# USBserial.net
KiCad netlist of a schematic drawn in Altium Designer
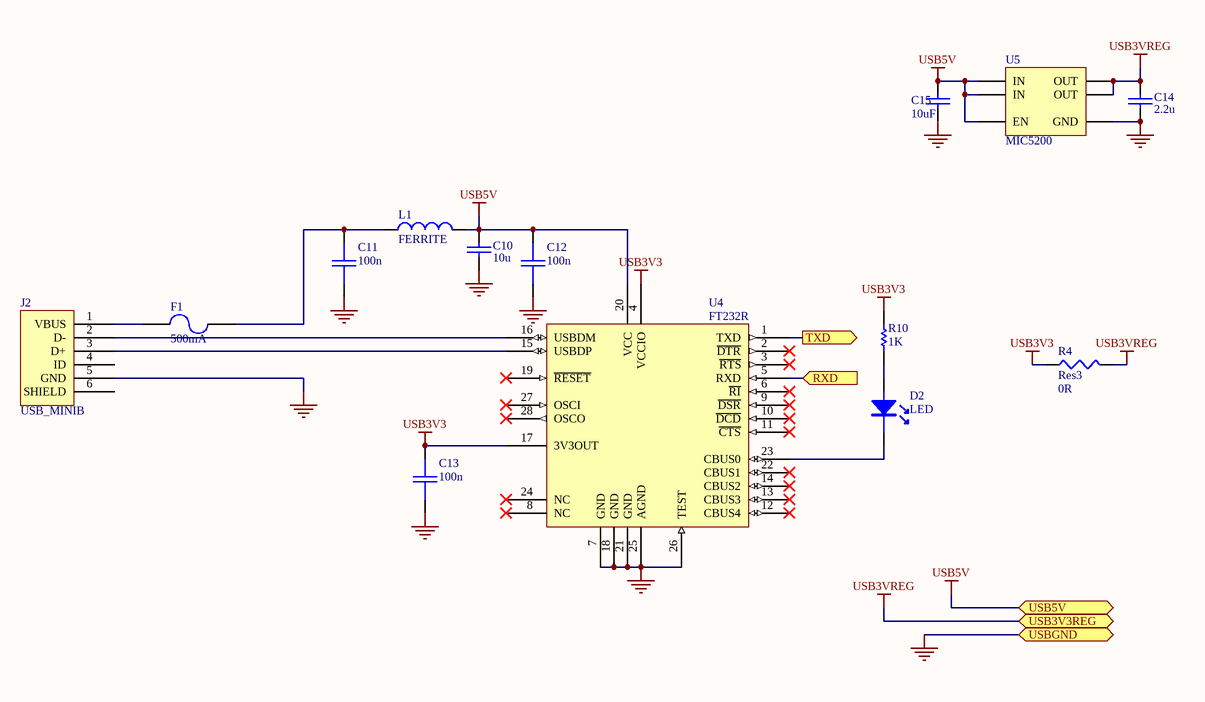
[diagram p0: USBserial.SchDoc]

(export (version "E")
  (design (tool "Eeschema 10.0.6"))
  (components
    (comp (ref "C10")
      (value "10u")
      (footprint "0805")
      (description "Capacitor")
      (libsource (lib "*") (part "CAP"))
    )
    (comp (ref "C11")
      (value "100n")
      (footprint "0603")
      (description "Capacitor")
      (libsource (lib "RCLDQ") (part "CAP"))
    )
    (comp (ref "C12")
      (value "100n")
      (footprint "0603")
      (description "Capacitor")
      (libsource (lib "RCLDQ") (part "CAP"))
    )
    (comp (ref "C13")
      (value "100n")
      (footprint "0603")
      (description "Capacitor")
      (libsource (lib "RCLDQ") (part "CAP"))
    )
    (comp (ref "C14")
      (value "2.2u")
      (footprint "0603")
      (description "Capacitor")
      (libsource (lib "*") (part "CAP"))
    )
    (comp (ref "C15")
      (value "10uF")
      (footprint "0805")
      (description "Capacitor")
      (fields (field (name "Comment") "10u"))
      (libsource (lib "*") (part "CAP"))
    )
    (comp (ref "D2") (value "LED") (footprint "3mmLED") (libsource (lib "RCLDQ") (part "LED")))
    (comp (ref "F1")
      (value "500mA")
      (footprint "LITTELFUSE-154")
      (description "Fuse")
      (libsource (lib "*") (part "FUSE2"))
    )
    (comp (ref "J2")
      (value "USB_MINIB")
      (footprint "Con USB:USB/SM0.8-6H5")
      (description "USB Mini B Connector")
      (libsource (lib "sion") (part "USB_miniB_SMT"))
    )
    (comp (ref "L1")
      (value "FERRITE")
      (footprint "0603")
      (description "Inductor")
      (fields (field (name "MANUFACTURER") "Generic Components"))
      (libsource (lib "RCLDQ") (part "INDUCTOR"))
    )
    (comp (ref "R4")
      (value "Res3")
      (footprint "0603")
      (description "Resistor")
      (fields (field (name "ALTIUM_VALUE") "0R") (field (name "PUBLISHER") "Altium Limited"))
      (libsource (lib "Miscellaneous Devices") (part "Res3"))
    )
    (comp (ref "R10")
      (value "1K")
      (footprint "0603")
      (description "Semiconductor Resistor")
      (libsource (lib "Miscellaneous Devices") (part "Res Semi"))
    )
    (comp (ref "U4")
      (value "FT232R")
      (footprint "SSOP28w")
      (description "USB UART IC")
      (libsource (lib "MiscellaneousIC") (part "FT232R"))
    )
    (comp (ref "U5")
      (value "MIC5200")
      (footprint "SO8")
      (description "MIC5200 - SO8")
      (libsource (lib "*") (part "MIC5200"))
    )
  )
  (nets
    (net (code "1") (name "/RXD") (class "Default")
      (node (ref "U4") (pin "5") (pinfunction "RXD_5") (pintype "input"))
    )
    (net (code "2") (name "/TXD") (class "Default")
      (node (ref "U4") (pin "1") (pinfunction "TXD_1") (pintype "output"))
    )
    (net (code "3") (name "Net-(C11-Pad1)") (class "Default")
      (node (ref "C11") (pin "1") (pinfunction "1_1") (pintype "passive"))
      (node (ref "F1") (pin "2") (pinfunction "2_2") (pintype "passive"))
      (node (ref "L1") (pin "1") (pinfunction "1_1") (pintype "passive"))
    )
    (net (code "4") (name "Net-(D2-PadA)") (class "Default")
      (node (ref "D2") (pin "A") (pinfunction "A_A") (pintype "passive"))
      (node (ref "R10") (pin "1") (pinfunction "1_1") (pintype "passive"))
    )
    (net (code "5") (name "Net-(J2-D+)") (class "Default")
      (node (ref "J2") (pin "3") (pinfunction "D+_3") (pintype "passive"))
      (node (ref "U4") (pin "15") (pinfunction "USBDP_15") (pintype "bidirectional"))
    )
    (net (code "6") (name "Net-(J2-D-)") (class "Default")
      (node (ref "J2") (pin "2") (pinfunction "D-_2") (pintype "passive"))
      (node (ref "U4") (pin "16") (pinfunction "USBDM_16") (pintype "bidirectional"))
    )
    (net (code "7") (name "Net-(J2-VBUS)") (class "Default")
      (node (ref "F1") (pin "1") (pinfunction "1_1") (pintype "passive"))
      (node (ref "J2") (pin "1") (pinfunction "VBUS_1") (pintype "passive"))
    )
    (net (code "8") (name "Net-(U4-CBUS0)") (class "Default")
      (node (ref "D2") (pin "K") (pinfunction "K_K") (pintype "passive"))
      (node (ref "U4") (pin "23") (pinfunction "CBUS0_23") (pintype "bidirectional"))
    )
    (net (code "9") (name "USB3V3") (class "Default")
      (node (ref "C13") (pin "1") (pinfunction "1_1") (pintype "passive"))
      (node (ref "R10") (pin "2") (pinfunction "2_2") (pintype "passive"))
      (node (ref "R4") (pin "1") (pinfunction "1_1") (pintype "passive"))
      (node (ref "U4") (pin "17") (pinfunction "3V3OUT_17") (pintype "power_in"))
      (node (ref "U4") (pin "4") (pinfunction "VCCIO_4") (pintype "power_in"))
    )
    (net (code "10") (name "USB3VREG") (class "Default")
      (node (ref "C14") (pin "2") (pinfunction "2_2") (pintype "passive"))
      (node (ref "R4") (pin "2") (pinfunction "2_2") (pintype "passive"))
      (node (ref "U5") (pin "1") (pinfunction "OUT_1") (pintype "passive"))
      (node (ref "U5") (pin "2") (pinfunction "OUT_2") (pintype "passive"))
    )
    (net (code "11") (name "USB5V") (class "Default")
      (node (ref "C10") (pin "2") (pinfunction "2_2") (pintype "passive"))
      (node (ref "C12") (pin "1") (pinfunction "1_1") (pintype "passive"))
      (node (ref "C15") (pin "1") (pinfunction "1_1") (pintype "passive"))
      (node (ref "L1") (pin "2") (pinfunction "2_2") (pintype "passive"))
      (node (ref "U4") (pin "20") (pinfunction "VCC_20") (pintype "power_in"))
      (node (ref "U5") (pin "5") (pinfunction "EN_5") (pintype "passive"))
      (node (ref "U5") (pin "7") (pinfunction "IN_7") (pintype "passive"))
      (node (ref "U5") (pin "8") (pinfunction "IN_8") (pintype "passive"))
    )
    (net (code "12") (name "USBGND") (class "Default")
      (node (ref "C10") (pin "1") (pinfunction "1_1") (pintype "passive"))
      (node (ref "C11") (pin "2") (pinfunction "2_2") (pintype "passive"))
      (node (ref "C12") (pin "2") (pinfunction "2_2") (pintype "passive"))
      (node (ref "C13") (pin "2") (pinfunction "2_2") (pintype "passive"))
      (node (ref "C14") (pin "1") (pinfunction "1_1") (pintype "passive"))
      (node (ref "C15") (pin "2") (pinfunction "2_2") (pintype "passive"))
      (node (ref "J2") (pin "5") (pinfunction "GND_5") (pintype "passive"))
      (node (ref "U4") (pin "18") (pinfunction "GND_18") (pintype "power_in"))
      (node (ref "U4") (pin "21") (pinfunction "GND_21") (pintype "power_in"))
      (node (ref "U4") (pin "25") (pinfunction "AGND_25") (pintype "power_in"))
      (node (ref "U4") (pin "26") (pinfunction "TEST_26") (pintype "input"))
      (node (ref "U4") (pin "7") (pinfunction "GND_7") (pintype "power_in"))
      (node (ref "U5") (pin "4") (pinfunction "GND_4") (pintype "passive"))
    )
    (net (code "13") (name "unconnected-(J2-ID-Pad4)") (class "Default")
      (node (ref "J2") (pin "4") (pinfunction "ID_4") (pintype "passive"))
    )
    (net (code "14") (name "unconnected-(J2-SHIELD-Pad6)") (class "Default")
      (node (ref "J2") (pin "6") (pinfunction "SHIELD_6") (pintype "passive"))
    )
    (net (code "15") (name "unconnected-(U4-CBUS1-Pad22)") (class "Default")
      (node (ref "U4") (pin "22") (pinfunction "CBUS1_22") (pintype "bidirectional+no_connect"))
    )
    (net (code "16") (name "unconnected-(U4-CBUS2-Pad14)") (class "Default")
      (node (ref "U4") (pin "14") (pinfunction "CBUS2_14") (pintype "bidirectional+no_connect"))
    )
    (net (code "17") (name "unconnected-(U4-CBUS3-Pad13)") (class "Default")
      (node (ref "U4") (pin "13") (pinfunction "CBUS3_13") (pintype "bidirectional+no_connect"))
    )
    (net (code "18") (name "unconnected-(U4-CBUS4-Pad12)") (class "Default")
      (node (ref "U4") (pin "12") (pinfunction "CBUS4_12") (pintype "bidirectional+no_connect"))
    )
    (net (code "19") (name "unconnected-(U4-NC-Pad8)") (class "Default")
      (node (ref "U4") (pin "8") (pinfunction "NC_8") (pintype "passive+no_connect"))
    )
    (net (code "20") (name "unconnected-(U4-NC-Pad24)") (class "Default")
      (node (ref "U4") (pin "24") (pinfunction "NC_24") (pintype "passive+no_connect"))
    )
    (net (code "21") (name "unconnected-(U4-OSCI-Pad27)") (class "Default")
      (node (ref "U4") (pin "27") (pinfunction "OSCI_27") (pintype "input+no_connect"))
    )
    (net (code "22") (name "unconnected-(U4-OSCO-Pad28)") (class "Default")
      (node (ref "U4") (pin "28") (pinfunction "OSCO_28") (pintype "output+no_connect"))
    )
    (net (code "23") (name "unconnected-(U4-~{CTS}-Pad11)") (class "Default")
      (node (ref "U4") (pin "11") (pinfunction "~{CTS}_11") (pintype "input+no_connect"))
    )
    (net (code "24") (name "unconnected-(U4-~{DCD}-Pad10)") (class "Default")
      (node (ref "U4") (pin "10") (pinfunction "~{DCD}_10") (pintype "input+no_connect"))
    )
    (net (code "25") (name "unconnected-(U4-~{DSR}-Pad9)") (class "Default")
      (node (ref "U4") (pin "9") (pinfunction "~{DSR}_9") (pintype "input+no_connect"))
    )
    (net (code "26") (name "unconnected-(U4-~{DTR}-Pad2)") (class "Default")
      (node (ref "U4") (pin "2") (pinfunction "~{DTR}_2") (pintype "output+no_connect"))
    )
    (net (code "27") (name "unconnected-(U4-~{RESET}-Pad19)") (class "Default")
      (node (ref "U4") (pin "19") (pinfunction "~{RESET}_19") (pintype "input+no_connect"))
    )
    (net (code "28") (name "unconnected-(U4-~{RI}-Pad6)") (class "Default")
      (node (ref "U4") (pin "6") (pinfunction "~{RI}_6") (pintype "input+no_connect"))
    )
    (net (code "29") (name "unconnected-(U4-~{RTS}-Pad3)") (class "Default")
      (node (ref "U4") (pin "3") (pinfunction "~{RTS}_3") (pintype "output+no_connect"))
    )
  )
)
